# 4_Analog_Circuits.net
KiCad netlist of a schematic drawn in Altium Designer
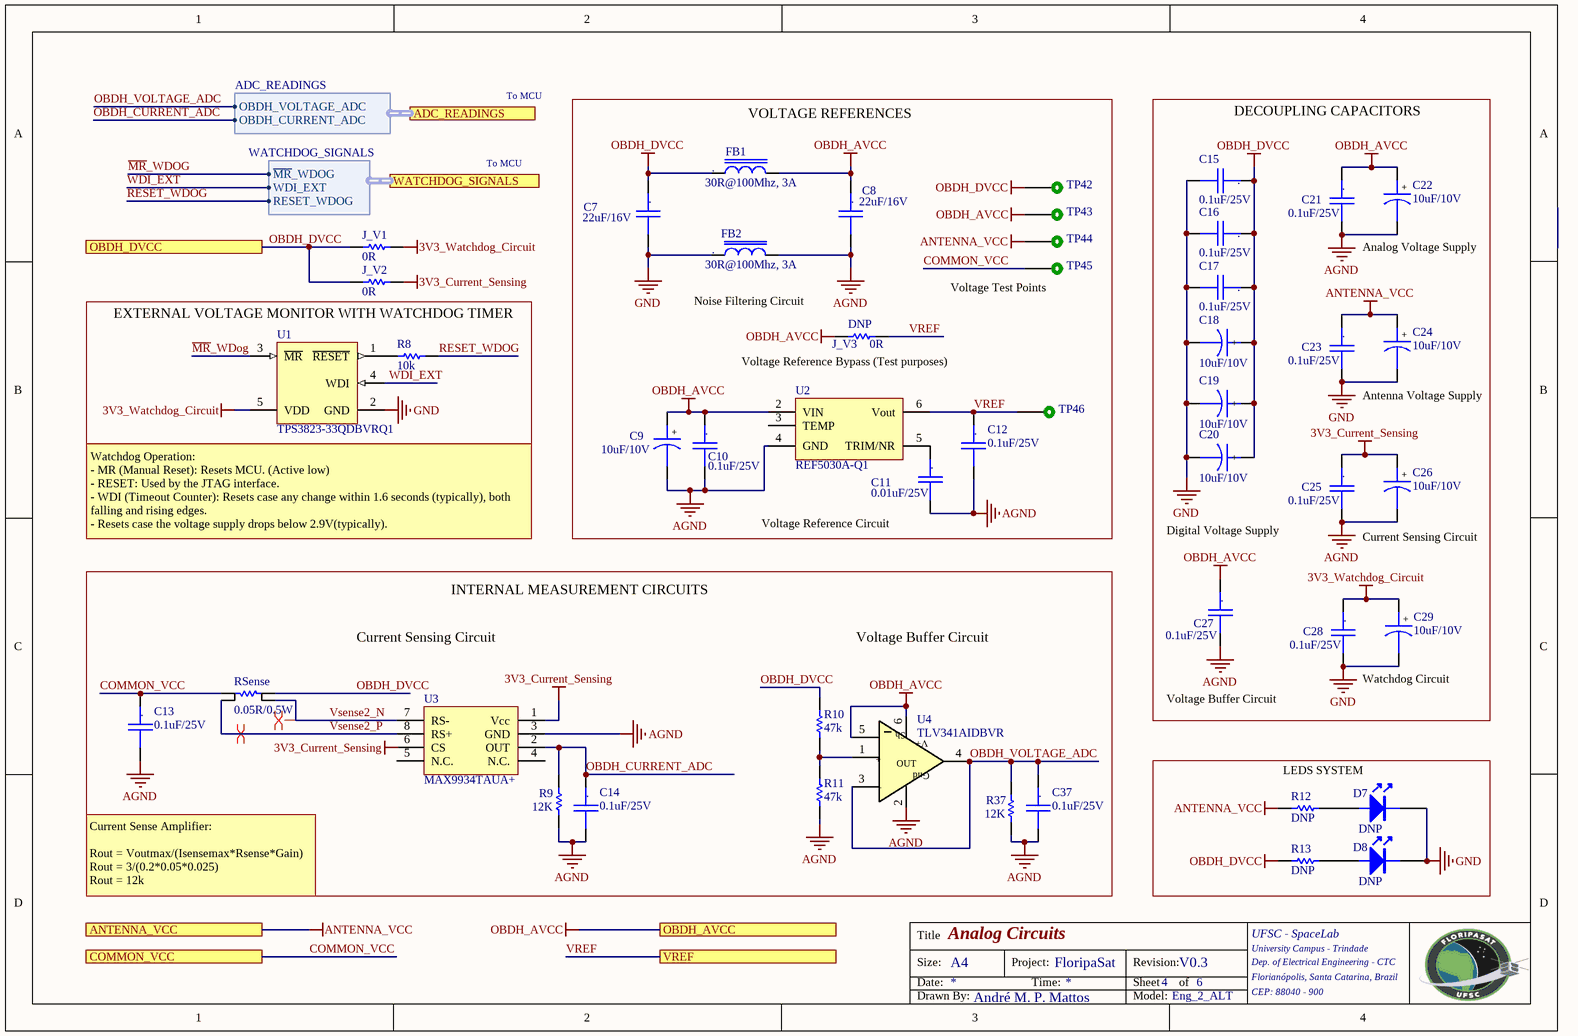
[diagram p0: 4_Analog_Circuits.SchDoc]

(export (version "E")
  (design (tool "Eeschema 10.0.6"))
  (components
    (comp (ref "C7")
      (value "22uF/16V")
      (footprint "CC1210")
      (description "CAP CER 22uF 16V 10% X7R 1210")
      (fields (field (name "PARTNUMBER") "C3225X7R1C226K250AC"))
      (libsource (lib "OBDH_Eng_Model_2_ALT") (part "Cap_Cer_X7R_0.01uF_16V_1210"))
    )
    (comp (ref "C8")
      (value "22uF/16V")
      (footprint "CC1210")
      (description "CAP CER 22uF 16V 10% X7R 1210")
      (fields (field (name "PARTNUMBER") "C3225X7R1C226K250AC"))
      (libsource (lib "OBDH_Eng_Model_2_ALT") (part "Cap_Cer_X7R_0.01uF_16V_1210"))
    )
    (comp (ref "C9")
      (value "10uF/10V")
      (footprint "CC0805_Tantalum")
      (description "CAP Tantalum 10uF 6.3V 10% 0805")
      (fields (field (name "PARTNUMBER") "TPSR106K006R1000"))
      (libsource (lib "OBDH_Eng_Model_2_ALT") (part "Cap_Tant_SMD_10uF_6V3_0805"))
    )
    (comp (ref "C10")
      (value "0.1uF/25V")
      (footprint "CC0805")
      (description "CAP CER 0.1UF 25V 10% X7R 0805")
      (fields (field (name "PARTNUMBER") "CC0805KRX7R8BB104"))
      (libsource (lib "OBDH_Eng_Model_2_ALT") (part "Cap_Cer_X7R_0.1uF_25V_0805"))
    )
    (comp (ref "C11")
      (value "0.01uF/25V")
      (footprint "CC0805")
      (description "CAP CER 0.01uF 25V 10% X7R 0805")
      (fields (field (name "PARTNUMBER") "CL21B103KAANNNC"))
      (libsource (lib "OBDH_Eng_Model_2_ALT") (part "Cap_Cer_X7R_0.01uF_50V_0805"))
    )
    (comp (ref "C12")
      (value "0.1uF/25V")
      (footprint "CC0805")
      (description "CAP CER 0.1UF 25V 10% X7R 0805")
      (fields (field (name "PARTNUMBER") "CC0805KRX7R8BB104"))
      (libsource (lib "OBDH_Eng_Model_2_ALT") (part "Cap_Cer_X7R_0.1uF_25V_0805"))
    )
    (comp (ref "C13")
      (value "0.1uF/25V")
      (footprint "CC0805")
      (description "CAP CER 0.1UF 25V 10% X7R 0805")
      (fields (field (name "PARTNUMBER") "CC0805KRX7R8BB104"))
      (libsource (lib "OBDH_Eng_Model_2_ALT") (part "Cap_Cer_X7R_0.1uF_25V_0805"))
    )
    (comp (ref "C14")
      (value "0.1uF/25V")
      (footprint "CC0805")
      (description "CAP CER 0.1UF 25V 10% X7R 0805")
      (fields (field (name "PARTNUMBER") "CC0805KRX7R8BB104"))
      (libsource (lib "OBDH_Eng_Model_2_ALT") (part "Cap_Cer_X7R_0.1uF_25V_0805"))
    )
    (comp (ref "C15")
      (value "0.1uF/25V")
      (footprint "CC0805")
      (description "CAP CER 0.1UF 25V 10% X7R 0805")
      (fields (field (name "PARTNUMBER") "CC0805KRX7R8BB104"))
      (libsource (lib "OBDH_Eng_Model_2_ALT") (part "Cap_Cer_X7R_0.1uF_25V_0805"))
    )
    (comp (ref "C16")
      (value "0.1uF/25V")
      (footprint "CC0805")
      (description "CAP CER 0.1UF 25V 10% X7R 0805")
      (fields (field (name "PARTNUMBER") "CC0805KRX7R8BB104"))
      (libsource (lib "OBDH_Eng_Model_2_ALT") (part "Cap_Cer_X7R_0.1uF_25V_0805"))
    )
    (comp (ref "C17")
      (value "0.1uF/25V")
      (footprint "CC0805")
      (description "CAP CER 0.1UF 25V 10% X7R 0805")
      (fields (field (name "PARTNUMBER") "CC0805KRX7R8BB104"))
      (libsource (lib "OBDH_Eng_Model_2_ALT") (part "Cap_Cer_X7R_0.1uF_25V_0805"))
    )
    (comp (ref "C18")
      (value "10uF/10V")
      (footprint "CC0805_Tantalum")
      (description "CAP Tantalum 10uF 6.3V 10% 0805")
      (fields (field (name "PARTNUMBER") "TPSR106K006R1000"))
      (libsource (lib "") (part "Cap_Tant_SMD_10uF_6V3_0805_1"))
    )
    (comp (ref "C19")
      (value "10uF/10V")
      (footprint "CC0805_Tantalum")
      (description "CAP Tantalum 10uF 6.3V 10% 0805")
      (fields (field (name "PARTNUMBER") "TPSR106K006R1000"))
      (libsource (lib "") (part "Cap_Tant_SMD_10uF_6V3_0805_1"))
    )
    (comp (ref "C20")
      (value "10uF/10V")
      (footprint "CC0805_Tantalum")
      (description "CAP Tantalum 10uF 6.3V 10% 0805")
      (fields (field (name "PARTNUMBER") "TPSR106K006R1000"))
      (libsource (lib "") (part "Cap_Tant_SMD_10uF_6V3_0805_1"))
    )
    (comp (ref "C21")
      (value "0.1uF/25V")
      (footprint "CC0805")
      (description "CAP CER 0.1UF 25V 10% X7R 0805")
      (fields (field (name "PARTNUMBER") "CC0805KRX7R8BB104"))
      (libsource (lib "OBDH_Eng_Model_2_ALT") (part "Cap_Cer_X7R_0.1uF_25V_0805"))
    )
    (comp (ref "C22")
      (value "10uF/10V")
      (footprint "CC0805_Tantalum")
      (description "CAP Tantalum 10uF 10V 20% 0805")
      (fields (field (name "PARTNUMBER") "TPSP106M010R2000"))
      (libsource (lib "OBDH_Eng_Model_2_ALT") (part "Cap_Tant_SMD_10uF_10V_0805"))
    )
    (comp (ref "C23")
      (value "0.1uF/25V")
      (footprint "CC0805")
      (description "CAP CER 0.1UF 25V 10% X7R 0805")
      (fields (field (name "PARTNUMBER") "CC0805KRX7R8BB104"))
      (libsource (lib "OBDH_Eng_Model_2_ALT") (part "Cap_Cer_X7R_0.1uF_25V_0805"))
    )
    (comp (ref "C24")
      (value "10uF/10V")
      (footprint "CC0805_Tantalum")
      (description "CAP Tantalum 10uF 10V 20% 0805")
      (fields (field (name "PARTNUMBER") "TPSP106M010R2000"))
      (libsource (lib "OBDH_Eng_Model_2_ALT") (part "Cap_Tant_SMD_10uF_10V_0805"))
    )
    (comp (ref "C25")
      (value "0.1uF/25V")
      (footprint "CC0805")
      (description "CAP CER 0.1UF 25V 10% X7R 0805")
      (fields (field (name "PARTNUMBER") "CC0805KRX7R8BB104"))
      (libsource (lib "OBDH_Eng_Model_2_ALT") (part "Cap_Cer_X7R_0.1uF_25V_0805"))
    )
    (comp (ref "C26")
      (value "10uF/10V")
      (footprint "CC0805_Tantalum")
      (description "CAP Tantalum 10uF 10V 20% 0805")
      (fields (field (name "PARTNUMBER") "TPSP106M010R2000"))
      (libsource (lib "OBDH_Eng_Model_2_ALT") (part "Cap_Tant_SMD_10uF_10V_0805"))
    )
    (comp (ref "C27")
      (value "0.1uF/25V")
      (footprint "CC0805")
      (description "CAP CER 0.1UF 25V 10% X7R 0805")
      (fields (field (name "PARTNUMBER") "CC0805KRX7R8BB104"))
      (libsource (lib "FloripaSatSchlib") (part "Cap_Cer_X7R_0.1uF_25V_0805"))
    )
    (comp (ref "C28")
      (value "0.1uF/25V")
      (footprint "CC0805")
      (description "CAP CER 0.1UF 25V 10% X7R 0805")
      (fields (field (name "PARTNUMBER") "CC0805KRX7R8BB104"))
      (libsource (lib "OBDH_Eng_Model_2_ALT") (part "Cap_Cer_X7R_0.1uF_25V_0805"))
    )
    (comp (ref "C29")
      (value "10uF/10V")
      (footprint "CC0805_Tantalum")
      (description "CAP Tantalum 10uF 10V 20% 0805")
      (fields (field (name "PARTNUMBER") "TPSP106M010R2000"))
      (libsource (lib "OBDH_Eng_Model_2_ALT") (part "Cap_Tant_SMD_10uF_10V_0805"))
    )
    (comp (ref "C37")
      (value "0.1uF/25V")
      (footprint "CC0805")
      (description "CAP CER 0.1UF 25V 10% X7R 0805")
      (fields (field (name "PARTNUMBER") "CC0805KRX7R8BB104"))
      (libsource (lib "OBDH_Eng_Model_2_ALT") (part "Cap_Cer_X7R_0.1uF_25V_0805"))
    )
    (comp (ref "D7")
      (value "DNP")
      (footprint "0805-LED")
      (description "SMD Green LED")
      (fields (field (name "PARTNUMBER") "LTST-C171GKT"))
      (libsource (lib "OBDH_Eng_Model_2_ALT") (part "LED/G_0805"))
    )
    (comp (ref "D8")
      (value "DNP")
      (footprint "0805-LED")
      (description "SMD Green LED")
      (fields (field (name "PARTNUMBER") "LTST-C171GKT"))
      (libsource (lib "OBDH_Eng_Model_2_ALT") (part "LED/G_0805"))
    )
    (comp (ref "FB1")
      (value "30R@100Mhz, 3A")
      (footprint "IND0805")
      (description "Ferrite Bead 30 OHM 3A 100MHz")
      (fields (field (name "PARTNUMBER") "BLM21PG300SN1D"))
      (libsource (lib "OBDH_Eng_Model_2_ALT") (part "FB_30R_3A_100MHz_0805"))
    )
    (comp (ref "FB2")
      (value "30R@100Mhz, 3A")
      (footprint "IND0805")
      (description "Ferrite Bead 30 OHM 3A 100MHz")
      (fields (field (name "PARTNUMBER") "BLM21PG300SN1D"))
      (libsource (lib "OBDH_Eng_Model_2_ALT") (part "FB_30R_3A_100MHz_0805"))
    )
    (comp (ref "J_V1")
      (value "0R")
      (footprint "0805")
      (description "RES 0R OHM 1/16W JUMPER 0805")
      (fields (field (name "PARTNUMBER") "CRCW08050000Z0EA"))
      (libsource (lib "OBDH_Eng_Model_2_ALT") (part "R0R_JUMPER_1/16W_0805"))
    )
    (comp (ref "J_V2")
      (value "0R")
      (footprint "0805")
      (description "RES 0R OHM 1/16W JUMPER 0805")
      (fields (field (name "PARTNUMBER") "CRCW08050000Z0EA"))
      (libsource (lib "OBDH_Eng_Model_2_ALT") (part "R0R_JUMPER_1/16W_0805"))
    )
    (comp (ref "J_V3")
      (value "0R")
      (footprint "0805")
      (description "RES 0R OHM 1/16W JUMPER 0805")
      (fields (field (name "PARTNUMBER") "CRCW08050000Z0EA"))
      (libsource (lib "OBDH_Eng_Model_2_ALT") (part "R0R_JUMPER_1/16W_0805"))
    )
    (comp (ref "R8")
      (value "10k")
      (footprint "0805")
      (description "RES 10K OHM 1/8W 1%  0805")
      (fields (field (name "PARTNUMBER") "CRCW080510K0FKEA"))
      (libsource (lib "OBDH_Eng_Model_2_ALT") (part "R10k_1%_1/8W_0805"))
    )
    (comp (ref "R9")
      (value "12K")
      (footprint "0805")
      (description "RES 1.65K OHM 1/10W 0.1% 0805")
      (fields (field (name "PARTNUMBER") "PCF0805R-1K65BT1"))
      (libsource (lib "OBDH_Eng_Model_2_ALT") (part "R1.65K_1%_1/10W_0805"))
    )
    (comp (ref "R10")
      (value "47k")
      (footprint "0805")
      (description "RES 47k OHM 1/10W 1% 0805")
      (fields (field (name "PARTNUMBER") "RC0805FR-0747KL"))
      (libsource (lib "OBDH_Eng_Model_2_ALT") (part "R27_5%_1/10W_0805"))
    )
    (comp (ref "R11")
      (value "47k")
      (footprint "0805")
      (description "RES 47k OHM 1/10W 1% 0805")
      (fields (field (name "PARTNUMBER") "RC0805FR-0747KL"))
      (libsource (lib "OBDH_Eng_Model_2_ALT") (part "R27_5%_1/10W_0805"))
    )
    (comp (ref "R12")
      (value "DNP")
      (footprint "0805")
      (description "RES 1.0K OHM 1/8W 1% 0805")
      (fields (field (name "PARTNUMBER") "RC0805FR-071KL"))
      (libsource (lib "OBDH_Eng_Model_2_ALT") (part "R1.0k_1%_1/8W_0805"))
    )
    (comp (ref "R13")
      (value "DNP")
      (footprint "0805")
      (description "RES 1.0K OHM 1/8W 1% 0805")
      (fields (field (name "PARTNUMBER") "RC0805FR-071KL"))
      (libsource (lib "OBDH_Eng_Model_2_ALT") (part "R1.0k_1%_1/8W_0805"))
    )
    (comp (ref "R37")
      (value "12K")
      (footprint "0805")
      (description "RES 1.65K OHM 1/10W 0.1% 0805")
      (fields (field (name "PARTNUMBER") "PCF0805R-1K65BT1"))
      (libsource (lib "OBDH_Eng_Model_2_ALT") (part "R1.65K_1%_1/10W_0805"))
    )
    (comp (ref "RSense")
      (value "0.05R/0.5W")
      (footprint "1206 - ohmite")
      (description "Current Sense Resistors - SMD 0.05ohm .5% 4 Terminal")
      (fields (field (name "PARTNUMBER") "LVK12R050DER"))
      (libsource (lib "OBDH_Eng_Model_2_ALT") (part "R0.05R_0.5%_0.5W_1206"))
    )
    (comp (ref "TP42")
      (value "TEST_POINT_2")
      (footprint "TEST_POINT_2")
      (description "Test point")
      (libsource (lib "OBDH_Eng_Model_2_ALT") (part "TEST_POINT_2"))
    )
    (comp (ref "TP43")
      (value "TEST_POINT_2")
      (footprint "TEST_POINT_2")
      (description "Test point")
      (libsource (lib "OBDH_Eng_Model_2_ALT") (part "TEST_POINT_2"))
    )
    (comp (ref "TP44")
      (value "TEST_POINT_2")
      (footprint "TEST_POINT_2")
      (description "Test point")
      (libsource (lib "OBDH_Eng_Model_2_ALT") (part "TEST_POINT_2"))
    )
    (comp (ref "TP45")
      (value "TEST_POINT_2")
      (footprint "TEST_POINT_2")
      (description "Test point")
      (libsource (lib "OBDH_Eng_Model_2_ALT") (part "TEST_POINT_2"))
    )
    (comp (ref "TP46")
      (value "TEST_POINT_2")
      (footprint "TEST_POINT_2")
      (description "Test point")
      (libsource (lib "OBDH_Eng_Model_2_ALT") (part "TEST_POINT_2"))
    )
    (comp (ref "U1")
      (value "TPS3823-33QDBVRQ1")
      (footprint "DBV0005A_N")
      (fields (field (name "MANUFACTURER") "Texas Instruments"))
      (libsource (lib "OBDH_Eng_Model_2_ALT") (part "CMP-0338-00011-2"))
    )
    (comp (ref "U2")
      (value "REF5030A-Q1")
      (footprint "SOIC-8")
      (libsource (lib "OBDH_Eng_Model_2_ALT") (part "REF5030A-Q1"))
    )
    (comp (ref "U3")
      (value "MAX9934TAUA+")
      (footprint "MSOP-8")
      (libsource (lib "OBDH_Eng_Model_2_ALT") (part "MAX9934TAUA+"))
    )
    (comp (ref "U4")
      (value "TLV341AIDBVR")
      (footprint "SOT-23 6L")
      (libsource (lib "OBDH_Eng_Model_2_ALT") (part "TLV341AIDBVR"))
    )
  )
  (nets
    (net (code "3") (name "/COMMON_VCC") (class "Default")
      (node (ref "C13") (pin "1") (pinfunction "1_1") (pintype "passive"))
      (node (ref "RSense") (pin "1") (pinfunction "1_1") (pintype "passive"))
      (node (ref "TP45") (pin "1") (pinfunction "1_1") (pintype "passive"))
    )
    (net (code "4") (name "/OBDH_CURRENT_ADC") (class "Default")
      (node (ref "C14") (pin "1") (pinfunction "1_1") (pintype "passive"))
      (node (ref "R9") (pin "2") (pinfunction "2_2") (pintype "passive"))
      (node (ref "U3") (pin "2") (pinfunction "OUT_2") (pintype "passive"))
    )
    (net (code "5") (name "/OBDH_VOLTAGE_ADC") (class "Default")
      (node (ref "C37") (pin "1") (pinfunction "1_1") (pintype "passive"))
      (node (ref "R37") (pin "2") (pinfunction "2_2") (pintype "passive"))
      (node (ref "U4") (pin "3") (pinfunction "-IN_3") (pintype "passive"))
      (node (ref "U4") (pin "4") (pinfunction "OUT_4") (pintype "passive"))
    )
    (net (code "6") (name "/RESET_WDOG") (class "Default")
      (node (ref "R8") (pin "2") (pinfunction "2_2") (pintype "passive"))
    )
    (net (code "7") (name "/VREF") (class "Default")
      (node (ref "C12") (pin "1") (pinfunction "1_1") (pintype "passive"))
      (node (ref "J_V3") (pin "1") (pinfunction "1_1") (pintype "passive"))
      (node (ref "TP46") (pin "1") (pinfunction "1_1") (pintype "passive"))
      (node (ref "U2") (pin "6") (pinfunction "Vout_6") (pintype "passive"))
    )
    (net (code "8") (name "/Vsense2_N") (class "Default")
      (node (ref "RSense") (pin "4") (pinfunction "4_4") (pintype "passive"))
      (node (ref "U3") (pin "7") (pinfunction "RS-_7") (pintype "passive"))
    )
    (net (code "9") (name "/Vsense2_P") (class "Default")
      (node (ref "RSense") (pin "3") (pinfunction "3_3") (pintype "passive"))
      (node (ref "U3") (pin "8") (pinfunction "RS+_8") (pintype "passive"))
    )
    (net (code "10") (name "/WDI_EXT") (class "Default")
      (node (ref "U1") (pin "4") (pinfunction "WDI_4") (pintype "input"))
    )
    (net (code "14") (name "/~{MR}_WDog") (class "Default")
      (node (ref "U1") (pin "3") (pinfunction "~{MR}_3") (pintype "input"))
    )
    (net (code "15") (name "3V3_Current_Sensing") (class "Default")
      (node (ref "C25") (pin "1") (pinfunction "1_1") (pintype "passive"))
      (node (ref "C26") (pin "1") (pinfunction "1_1") (pintype "passive"))
      (node (ref "J_V2") (pin "1") (pinfunction "1_1") (pintype "passive"))
      (node (ref "U3") (pin "1") (pinfunction "Vcc_1") (pintype "passive"))
    )
    (net (code "16") (name "3V3_Watchdog_Circuit") (class "Default")
      (node (ref "C28") (pin "1") (pinfunction "1_1") (pintype "passive"))
      (node (ref "C29") (pin "1") (pinfunction "1_1") (pintype "passive"))
      (node (ref "J_V1") (pin "1") (pinfunction "1_1") (pintype "passive"))
      (node (ref "U1") (pin "5") (pinfunction "VDD_5") (pintype "power_in"))
    )
    (net (code "17") (name "AGND") (class "Default")
      (node (ref "C10") (pin "2") (pinfunction "2_2") (pintype "passive"))
      (node (ref "C11") (pin "2") (pinfunction "2_2") (pintype "passive"))
      (node (ref "C12") (pin "2") (pinfunction "2_2") (pintype "passive"))
      (node (ref "C13") (pin "2") (pinfunction "2_2") (pintype "passive"))
      (node (ref "C14") (pin "2") (pinfunction "2_2") (pintype "passive"))
      (node (ref "C21") (pin "2") (pinfunction "2_2") (pintype "passive"))
      (node (ref "C22") (pin "2") (pinfunction "2_2") (pintype "passive"))
      (node (ref "C25") (pin "2") (pinfunction "2_2") (pintype "passive"))
      (node (ref "C26") (pin "2") (pinfunction "2_2") (pintype "passive"))
      (node (ref "C27") (pin "2") (pinfunction "2_2") (pintype "passive"))
      (node (ref "C37") (pin "2") (pinfunction "2_2") (pintype "passive"))
      (node (ref "C8") (pin "2") (pinfunction "2_2") (pintype "passive"))
      (node (ref "C9") (pin "2") (pinfunction "2_2") (pintype "passive"))
      (node (ref "FB2") (pin "2") (pinfunction "2_2") (pintype "passive"))
      (node (ref "R11") (pin "1") (pinfunction "1_1") (pintype "passive"))
      (node (ref "R37") (pin "1") (pinfunction "1_1") (pintype "passive"))
      (node (ref "R9") (pin "1") (pinfunction "1_1") (pintype "passive"))
      (node (ref "U2") (pin "4") (pinfunction "GND_4") (pintype "passive"))
      (node (ref "U3") (pin "3") (pinfunction "GND_3") (pintype "passive"))
      (node (ref "U4") (pin "2") (pinfunction "Gnd_2") (pintype "passive"))
    )
    (net (code "18") (name "ANTENNA_VCC") (class "Default")
      (node (ref "C23") (pin "1") (pinfunction "1_1") (pintype "passive"))
      (node (ref "C24") (pin "1") (pinfunction "1_1") (pintype "passive"))
      (node (ref "R12") (pin "2") (pinfunction "2_2") (pintype "passive"))
      (node (ref "TP44") (pin "1") (pinfunction "1_1") (pintype "passive"))
    )
    (net (code "19") (name "GND") (class "Default")
      (node (ref "C15") (pin "2") (pinfunction "2_2") (pintype "passive"))
      (node (ref "C16") (pin "2") (pinfunction "2_2") (pintype "passive"))
      (node (ref "C17") (pin "2") (pinfunction "2_2") (pintype "passive"))
      (node (ref "C18") (pin "2") (pinfunction "2_2") (pintype "passive"))
      (node (ref "C19") (pin "2") (pinfunction "2_2") (pintype "passive"))
      (node (ref "C20") (pin "2") (pinfunction "2_2") (pintype "passive"))
      (node (ref "C23") (pin "2") (pinfunction "2_2") (pintype "passive"))
      (node (ref "C24") (pin "2") (pinfunction "2_2") (pintype "passive"))
      (node (ref "C28") (pin "2") (pinfunction "2_2") (pintype "passive"))
      (node (ref "C29") (pin "2") (pinfunction "2_2") (pintype "passive"))
      (node (ref "C7") (pin "2") (pinfunction "2_2") (pintype "passive"))
      (node (ref "D7") (pin "2") (pinfunction "K_2") (pintype "passive"))
      (node (ref "D8") (pin "2") (pinfunction "K_2") (pintype "passive"))
      (node (ref "FB2") (pin "1") (pinfunction "1_1") (pintype "passive"))
      (node (ref "U1") (pin "2") (pinfunction "GND_2") (pintype "power_in"))
    )
    (net (code "20") (name "Net-(D7-A)") (class "Default")
      (node (ref "D7") (pin "1") (pinfunction "A_1") (pintype "passive"))
      (node (ref "R12") (pin "1") (pinfunction "1_1") (pintype "passive"))
    )
    (net (code "21") (name "Net-(D8-A)") (class "Default")
      (node (ref "D8") (pin "1") (pinfunction "A_1") (pintype "passive"))
      (node (ref "R13") (pin "1") (pinfunction "1_1") (pintype "passive"))
    )
    (net (code "22") (name "Net-(U1-~{RESET})") (class "Default")
      (node (ref "R8") (pin "1") (pinfunction "1_1") (pintype "passive"))
      (node (ref "U1") (pin "1") (pinfunction "~{RESET}_1") (pintype "output"))
    )
    (net (code "23") (name "Net-(U2-TRIM{slash}NR)") (class "Default")
      (node (ref "C11") (pin "1") (pinfunction "1_1") (pintype "passive"))
      (node (ref "U2") (pin "5") (pinfunction "TRIM/NR_5") (pintype "passive"))
    )
    (net (code "24") (name "Net-(U4-+IN)") (class "Default")
      (node (ref "R10") (pin "1") (pinfunction "1_1") (pintype "passive"))
      (node (ref "R11") (pin "2") (pinfunction "2_2") (pintype "passive"))
      (node (ref "U4") (pin "1") (pinfunction "+IN_1") (pintype "passive"))
    )
    (net (code "25") (name "OBDH_AVCC") (class "Default")
      (node (ref "C10") (pin "1") (pinfunction "1_1") (pintype "passive"))
      (node (ref "C21") (pin "1") (pinfunction "1_1") (pintype "passive"))
      (node (ref "C22") (pin "1") (pinfunction "1_1") (pintype "passive"))
      (node (ref "C27") (pin "1") (pinfunction "1_1") (pintype "passive"))
      (node (ref "C8") (pin "1") (pinfunction "1_1") (pintype "passive"))
      (node (ref "C9") (pin "1") (pinfunction "1_1") (pintype "passive"))
      (node (ref "FB1") (pin "2") (pinfunction "2_2") (pintype "passive"))
      (node (ref "J_V3") (pin "2") (pinfunction "2_2") (pintype "passive"))
      (node (ref "TP43") (pin "1") (pinfunction "1_1") (pintype "passive"))
      (node (ref "U2") (pin "2") (pinfunction "VIN_2") (pintype "passive"))
      (node (ref "U4") (pin "5") (pinfunction "EN_5") (pintype "passive"))
      (node (ref "U4") (pin "6") (pinfunction "V+_6") (pintype "passive"))
    )
    (net (code "26") (name "OBDH_DVCC") (class "Default")
      (node (ref "C15") (pin "1") (pinfunction "1_1") (pintype "passive"))
      (node (ref "C16") (pin "1") (pinfunction "1_1") (pintype "passive"))
      (node (ref "C17") (pin "1") (pinfunction "1_1") (pintype "passive"))
      (node (ref "C18") (pin "1") (pinfunction "1_1") (pintype "passive"))
      (node (ref "C19") (pin "1") (pinfunction "1_1") (pintype "passive"))
      (node (ref "C20") (pin "1") (pinfunction "1_1") (pintype "passive"))
      (node (ref "C7") (pin "1") (pinfunction "1_1") (pintype "passive"))
      (node (ref "FB1") (pin "1") (pinfunction "1_1") (pintype "passive"))
      (node (ref "J_V1") (pin "2") (pinfunction "2_2") (pintype "passive"))
      (node (ref "J_V2") (pin "2") (pinfunction "2_2") (pintype "passive"))
      (node (ref "R10") (pin "2") (pinfunction "2_2") (pintype "passive"))
      (node (ref "R13") (pin "2") (pinfunction "2_2") (pintype "passive"))
      (node (ref "RSense") (pin "2") (pinfunction "2_2") (pintype "passive"))
      (node (ref "TP42") (pin "1") (pinfunction "1_1") (pintype "passive"))
    )
    (net (code "27") (name "unconnected-(U2-TEMP-Pad3)") (class "Default")
      (node (ref "U2") (pin "3") (pinfunction "TEMP_3") (pintype "passive"))
    )
    (net (code "28") (name "unconnected-(U3-CS-Pad6)") (class "Default")
      (node (ref "U3") (pin "6") (pinfunction "CS_6") (pintype "passive"))
    )
    (net (code "29") (name "unconnected-(U3-N.C.-Pad4)") (class "Default")
      (node (ref "U3") (pin "4") (pinfunction "N.C._4") (pintype "passive"))
    )
    (net (code "30") (name "unconnected-(U3-N.C.-Pad5)") (class "Default")
      (node (ref "U3") (pin "5") (pinfunction "N.C._5") (pintype "passive"))
    )
  )
)
